# Arduino_S3v3_R2.net
KiCad netlist of a schematic drawn in EAGLE
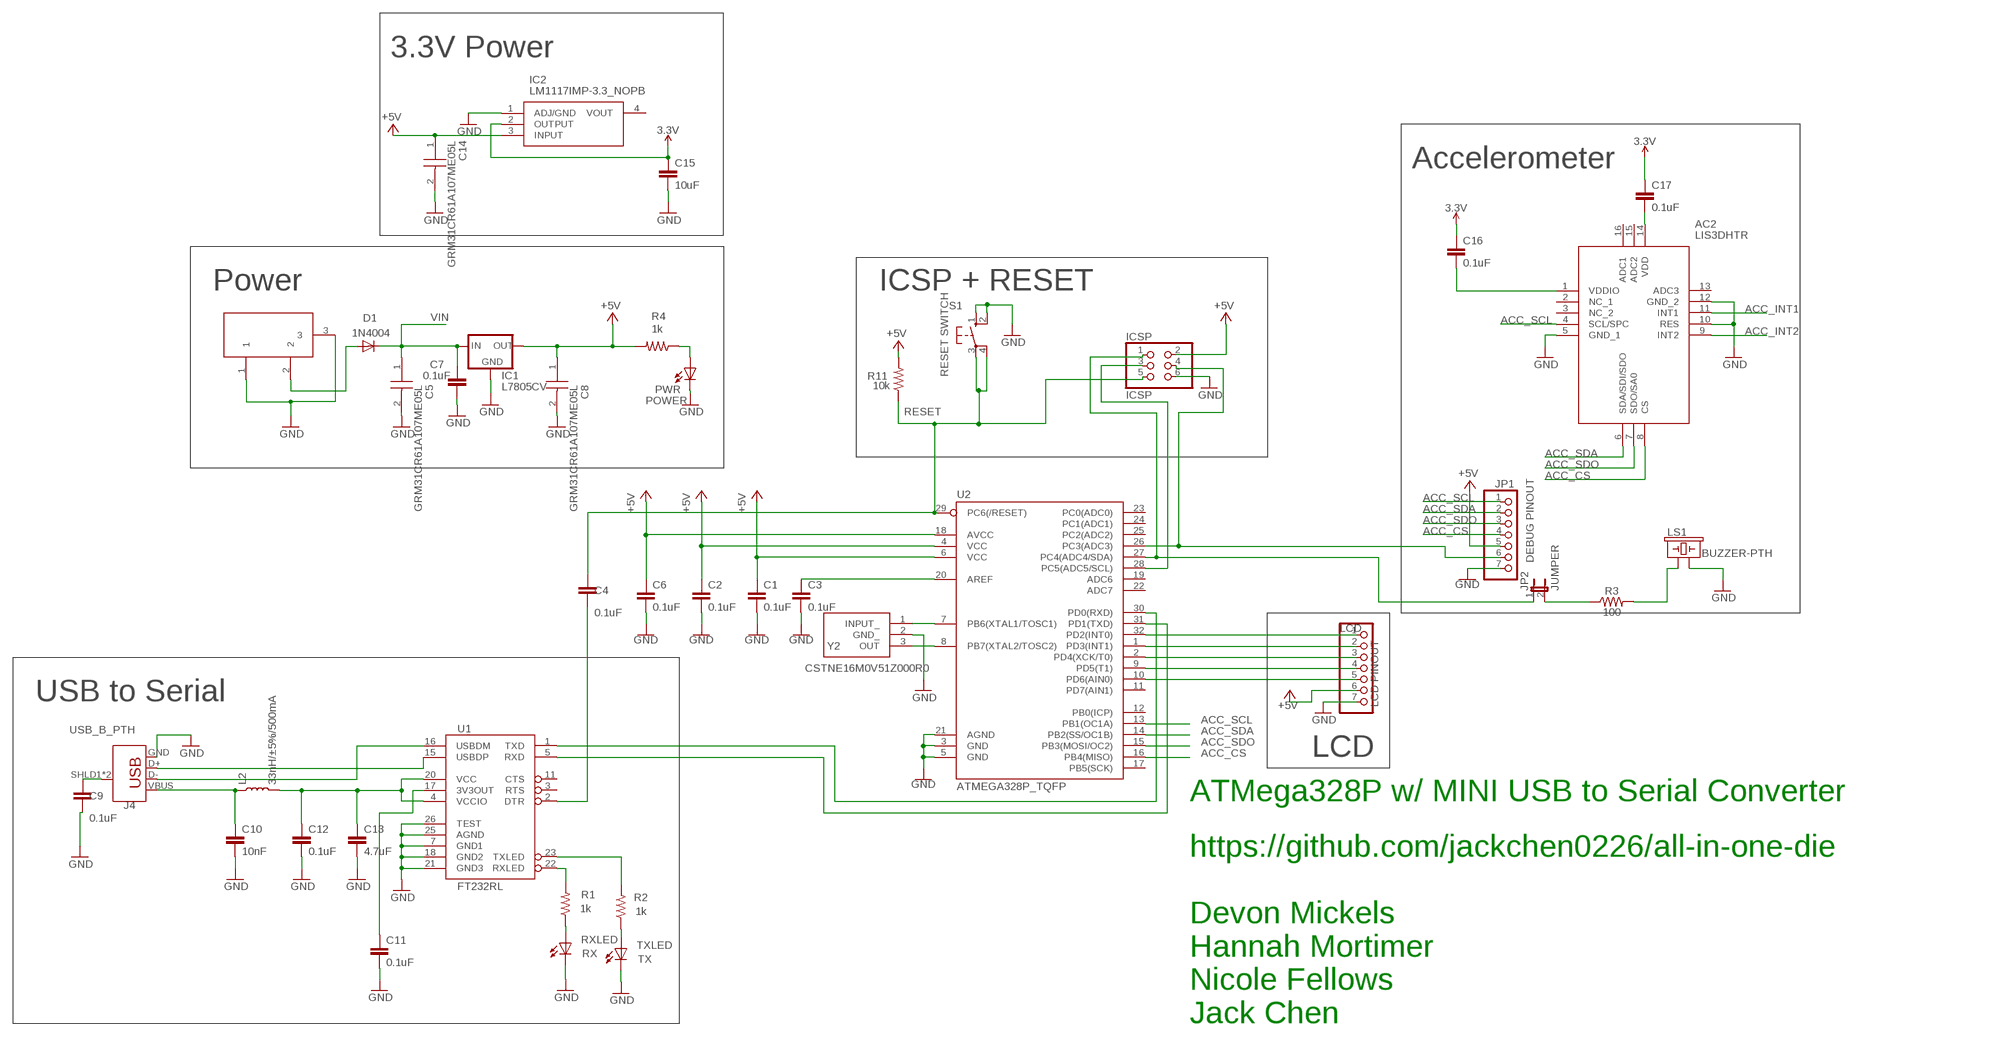
[diagram p0: schematic, sheet 1]

(export (version "E")
  (design (tool "Eeschema 10.0.6"))
  (components
    (comp (ref "AC2")
      (value "LIS3DHTR")
      (footprint "eagle-import:LIS3DHTR")
      (fields (field (name "MOUSER_PART_NUMBER") "511-LIS3DHTR"))
      (libsource (lib "eagle-import") (part "LIS3DHTR"))
    )
    (comp (ref "C1")
      (value "0.1uF")
      (footprint "eagle-import:0603")
      (fields (field (name "MFR") "KEMET") (field (name "MPN") "C0603X104K5RAC3316"))
      (libsource (lib "eagle-import") (part "0.1UF-0603-25V-(+80/-20%)"))
    )
    (comp (ref "C2")
      (value "0.1uF")
      (footprint "eagle-import:0603")
      (fields (field (name "MFR") "KEMET") (field (name "MPN") "C0603X104K5RAC3316"))
      (libsource (lib "eagle-import") (part "0.1UF-0603-25V-(+80/-20%)"))
    )
    (comp (ref "C3")
      (value "0.1uF")
      (footprint "eagle-import:0603")
      (fields (field (name "MFR") "KEMET") (field (name "MPN") "C0603X104K5RAC3316"))
      (libsource (lib "eagle-import") (part "0.1UF-0603-25V-(+80/-20%)"))
    )
    (comp (ref "C4")
      (value "0.1uF")
      (footprint "eagle-import:0603")
      (fields (field (name "MFR") "KEMET") (field (name "MPN") "C0603X104K5RAC3316"))
      (libsource (lib "eagle-import") (part "0.1UF-0603-25V-(+80/-20%)"))
    )
    (comp (ref "C5")
      (value "GRM31CR61A107ME05L")
      (footprint "eagle-import:CAPC3216X180N")
      (fields (field (name "MOUSER_PART_NUMBER") "81-GRM31CR61A107ME5L"))
      (libsource (lib "eagle-import") (part "GRM31CR61A107ME05L"))
    )
    (comp (ref "C6")
      (value "0.1uF")
      (footprint "eagle-import:0603")
      (fields (field (name "MFR") "KEMET") (field (name "MPN") "C0603X104K5RAC3316"))
      (libsource (lib "eagle-import") (part "0.1UF-0603-25V-(+80/-20%)"))
    )
    (comp (ref "C7")
      (value "0.1uF")
      (footprint "eagle-import:0603")
      (fields (field (name "MFR") "KEMET") (field (name "MPN") "C0603X104K5RAC3316"))
      (libsource (lib "eagle-import") (part "0.1UF-0603-25V-(+80/-20%)"))
    )
    (comp (ref "C8")
      (value "GRM31CR61A107ME05L")
      (footprint "eagle-import:CAPC3216X180N")
      (fields (field (name "MOUSER_PART_NUMBER") "81-GRM31CR61A107ME5L"))
      (libsource (lib "eagle-import") (part "GRM31CR61A107ME05L"))
    )
    (comp (ref "C9")
      (value "0.1uF")
      (footprint "eagle-import:0603")
      (fields (field (name "MFR") "KEMET") (field (name "MPN") "C0603X104K5RAC3316"))
      (libsource (lib "eagle-import") (part "0.1UF-0603-25V-(+80/-20%)"))
    )
    (comp (ref "C10")
      (value "10nF")
      (footprint "eagle-import:0603")
      (fields (field (name "MFR") "KEMET") (field (name "MPN") "C0603C103K5RAC7013"))
      (libsource (lib "eagle-import") (part "10NF-0603-50V-10%"))
    )
    (comp (ref "C11")
      (value "0.1uF")
      (footprint "eagle-import:0603")
      (fields (field (name "MFR") "KEMET") (field (name "MPN") "C0603X104K5RAC3316"))
      (libsource (lib "eagle-import") (part "0.1UF-0603-25V-(+80/-20%)"))
    )
    (comp (ref "C12")
      (value "0.1uF")
      (footprint "eagle-import:0603")
      (fields (field (name "MFR") "KEMET") (field (name "MPN") "C0603X104K5RAC3316"))
      (libsource (lib "eagle-import") (part "0.1UF-0603-25V-(+80/-20%)"))
    )
    (comp (ref "C13")
      (value "4.7uF")
      (footprint "eagle-import:0603")
      (fields (field (name "MFR") "Taiyo Yuden") (field (name "MPN") "LMK107BJ475MAHT"))
      (libsource (lib "eagle-import") (part "4.7UF0603"))
    )
    (comp (ref "C14")
      (value "GRM31CR61A107ME05L")
      (footprint "eagle-import:CAPC3216X180N")
      (fields (field (name "MOUSER_PART_NUMBER") "81-GRM31CR61A107ME5L"))
      (libsource (lib "eagle-import") (part "GRM31CR61A107ME05L"))
    )
    (comp (ref "C15")
      (value "10uF")
      (footprint "eagle-import:0603")
      (fields (field (name "MFR") "Murata Electronics") (field (name "MPN") "GRM188R61E106KA73D"))
      (libsource (lib "eagle-import") (part "10UF-0603-6.3V-20%"))
    )
    (comp (ref "C16")
      (value "0.1uF")
      (footprint "eagle-import:0603")
      (fields (field (name "MFR") "KEMET") (field (name "MPN") "C0603X104K5RAC3316"))
      (libsource (lib "eagle-import") (part "0.1UF-0603-25V-(+80/-20%)"))
    )
    (comp (ref "C17")
      (value "0.1uF")
      (footprint "eagle-import:0603")
      (fields (field (name "MFR") "KEMET") (field (name "MPN") "C0603X104K5RAC3316"))
      (libsource (lib "eagle-import") (part "0.1UF-0603-25V-(+80/-20%)"))
    )
    (comp (ref "D1")
      (value "1N4004")
      (footprint "eagle-import:DO41-10")
      (fields (field (name "MFR") "Diodes Incorporated") (field (name "MPN") "1N4004-T"))
      (libsource (lib "eagle-import") (part "1N4004"))
    )
    (comp (ref "DC1")
      (value "DC21MMX")
      (footprint "eagle-import:DC-21MM")
      (fields (field (name "MFR") "Gravitech") (field (name "MPN") "CON-SOCJ-2155"))
      (libsource (lib "eagle-import") (part "DC21MMX"))
    )
    (comp (ref "IC1")
      (value "L7805CV")
      (footprint "eagle-import:78XXS")
      (fields (field (name "MFR") "STMicroelectronics"))
      (libsource (lib "eagle-import") (part "78XXS"))
    )
    (comp (ref "IC2")
      (value "LM1117IMP-3.3_NOPB")
      (footprint "eagle-import:SOT230P700X180-4N")
      (fields
        (field (name "MANUFACTURER_PART_NUMBER") "LM1117IMP-3.3/NOPB")
        (field (name "MOUSER_PART_NUMBER") "926-LM1117IMP3.3NOPB")
      )
      (libsource (lib "eagle-import") (part "LM1117IMP-3.3_NOPB"))
    )
    (comp (ref "ICSP")
      (value "ICSP")
      (footprint "eagle-import:2X03")
      (fields (field (name "MFR") "Harwin") (field (name "MPN") "M20-9980346"))
      (libsource (lib "eagle-import") (part "PINHD-2X3"))
    )
    (comp (ref "J4")
      (value "USB_B_PTH")
      (footprint "eagle-import:USB-B-PTH")
      (fields (field (name "MFR") "Amphenol FCI") (field (name "MPN") "61729-0010BLF"))
      (libsource (lib "eagle-import") (part "USB_B_PTH"))
    )
    (comp (ref "JP1")
      (value "DEBUG PINOUT")
      (footprint "eagle-import:1X07")
      (fields (field (name "MFR") "Harwin") (field (name "MPN") "M20-9770746"))
      (libsource (lib "eagle-import") (part "PINHD-1X7"))
    )
    (comp (ref "JP2")
      (value "JUMPER")
      (footprint "eagle-import:JP1")
      (fields (field (name "MFR") "Harwin") (field (name "MPN") "M20-9990246"))
      (libsource (lib "eagle-import") (part "JP1E"))
    )
    (comp (ref "L2")
      (value "33nH/±5%/500mA")
      (footprint "eagle-import:0603")
      (fields (field (name "MFR") "Murata Electronics") (field (name "MPN") "LQW18AS33NJ0CD"))
      (libsource (lib "eagle-import") (part "INDUCTOR-0603-33NH"))
    )
    (comp (ref "LCD")
      (value "LCD PINOUT")
      (footprint "eagle-import:1X07")
      (fields (field (name "MFR") "Harwin") (field (name "MPN") "M20-9770746"))
      (libsource (lib "eagle-import") (part "PINHD-1X7"))
    )
    (comp (ref "LS1")
      (value "BUZZER-PTH")
      (footprint "eagle-import:BUZZER-12MM")
      (fields (field (name "MFR") "TDK") (field (name "MPN") "SD1209T5-A1"))
      (libsource (lib "eagle-import") (part "BUZZER-PTH"))
    )
    (comp (ref "PWR")
      (value "POWER")
      (footprint "eagle-import:LED3MM")
      (fields (field (name "MFR") "VCC") (field (name "MPN") "LTH3MM12VFR4100"))
      (libsource (lib "eagle-import") (part "LED3MM"))
    )
    (comp (ref "R1")
      (value "1k")
      (footprint "eagle-import:0603")
      (fields (field (name "MFR") "Vishay / Dale") (field (name "MPN") "RCC06031K00FKEA"))
      (libsource (lib "eagle-import") (part "1KOHM-0603-1/10W-1%"))
    )
    (comp (ref "R2")
      (value "1k")
      (footprint "eagle-import:0603")
      (fields (field (name "MFR") "Vishay / Dale") (field (name "MPN") "RCC06031K00FKEA"))
      (libsource (lib "eagle-import") (part "1KOHM-0603-1/10W-1%"))
    )
    (comp (ref "R3")
      (value "100")
      (footprint "eagle-import:0603")
      (fields (field (name "MFR") "Vishay / Dale") (field (name "MPN") "RCC0603100RFKEA"))
      (libsource (lib "eagle-import") (part "100OHM-0603-1/4W-5%"))
    )
    (comp (ref "R4")
      (value "1k")
      (footprint "eagle-import:0603")
      (fields (field (name "MFR") "Vishay / Dale") (field (name "MPN") "RCC06031K00FKEA"))
      (libsource (lib "eagle-import") (part "1KOHM-0603-1/10W-1%"))
    )
    (comp (ref "R11")
      (value "10k")
      (footprint "eagle-import:0603")
      (fields (field (name "MFR") "Panasonic") (field (name "MPN") "ERJ-UP3D1002V"))
      (libsource (lib "eagle-import") (part "10KOHM-0603-1/10W-1%"))
    )
    (comp (ref "RXLED")
      (value "RX")
      (footprint "eagle-import:LED3MM")
      (fields (field (name "MFR") "VCC") (field (name "MPN") "LTH3MM12VFR4500"))
      (libsource (lib "eagle-import") (part "LED3MM"))
    )
    (comp (ref "S1")
      (value "RESET SWITCH")
      (footprint "eagle-import:B3F-10XX")
      (fields (field (name "MFR") "Omron Electronics") (field (name "MPN") "B3F-1000"))
      (libsource (lib "eagle-import") (part "10-XX"))
    )
    (comp (ref "TXLED")
      (value "TX")
      (footprint "eagle-import:LED3MM")
      (fields (field (name "MFR") "VCC") (field (name "MPN") "LTH3MM12VFR4500"))
      (libsource (lib "eagle-import") (part "LED3MM"))
    )
    (comp (ref "U1")
      (value "FT232RL")
      (footprint "eagle-import:SSOP28DB")
      (fields (field (name "MFR") "FTDI") (field (name "MPN") "FT232RL-REEL"))
      (libsource (lib "eagle-import") (part "FT232RL-BASICSSOP"))
    )
    (comp (ref "U2")
      (value "ATMEGA328P_TQFP")
      (footprint "eagle-import:TQFP32-08")
      (fields (field (name "MFR") "Microchip Technology / Atmel") (field (name "MPN") "ATMEGA328P-AU"))
      (libsource (lib "eagle-import") (part "ATMEGA328P_TQFP"))
    )
    (comp (ref "Y2")
      (value "CSTNE16M0V51Z000R0")
      (footprint "eagle-import:CSTNE16M0V51Z000R0")
      (fields (field (name "MOUSER_PART_NUMBER") "81-CSTNE16M0V51Z000R"))
      (libsource (lib "eagle-import") (part "CSTNE16M0V51Z000R0"))
    )
  )
  (nets
    (net (code "1") (name "+5V") (class "Default")
      (node (ref "C1") (pin "1") (pinfunction "1_1") (pintype "passive"))
      (node (ref "C14") (pin "1") (pinfunction "1_1") (pintype "bidirectional"))
      (node (ref "C2") (pin "1") (pinfunction "1_1") (pintype "passive"))
      (node (ref "C6") (pin "1") (pinfunction "1_1") (pintype "passive"))
      (node (ref "C8") (pin "1") (pinfunction "1_1") (pintype "bidirectional"))
      (node (ref "IC1") (pin "OUT") (pinfunction "OUT_OUT") (pintype "passive"))
      (node (ref "IC2") (pin "3") (pinfunction "INPUT_3") (pintype "bidirectional"))
      (node (ref "ICSP") (pin "2") (pinfunction "2_2") (pintype "passive"))
      (node (ref "JP1") (pin "5") (pinfunction "5_5") (pintype "passive"))
      (node (ref "LCD") (pin "6") (pinfunction "6_6") (pintype "passive"))
      (node (ref "R11") (pin "2") (pinfunction "2_2") (pintype "passive"))
      (node (ref "R4") (pin "2") (pinfunction "2_2") (pintype "passive"))
      (node (ref "U2") (pin "18") (pinfunction "AVCC_18") (pintype "bidirectional"))
      (node (ref "U2") (pin "4") (pinfunction "VCC_4") (pintype "bidirectional"))
      (node (ref "U2") (pin "6") (pinfunction "VCC_6") (pintype "bidirectional"))
    )
    (net (code "2") (name "/ACC_CS") (class "Default")
      (node (ref "AC2") (pin "8") (pinfunction "CS_8") (pintype "input"))
      (node (ref "JP1") (pin "4") (pinfunction "4_4") (pintype "passive"))
      (node (ref "U2") (pin "16") (pinfunction "PB4(MISO)_16") (pintype "bidirectional"))
    )
    (net (code "3") (name "/ACC_INT1") (class "Default")
      (node (ref "AC2") (pin "11") (pinfunction "INT1_11") (pintype "input"))
    )
    (net (code "4") (name "/ACC_INT2") (class "Default")
      (node (ref "AC2") (pin "9") (pinfunction "INT2_9") (pintype "input"))
    )
    (net (code "5") (name "/ACC_SCL") (class "Default")
      (node (ref "AC2") (pin "4") (pinfunction "SCL/SPC_4") (pintype "bidirectional"))
      (node (ref "JP1") (pin "1") (pinfunction "1_1") (pintype "passive"))
      (node (ref "U2") (pin "13") (pinfunction "PB1(OC1A)_13") (pintype "bidirectional"))
    )
    (net (code "6") (name "/ACC_SDA") (class "Default")
      (node (ref "AC2") (pin "6") (pinfunction "SDA/SDI/SDO_6") (pintype "bidirectional"))
      (node (ref "JP1") (pin "2") (pinfunction "2_2") (pintype "passive"))
      (node (ref "U2") (pin "14") (pinfunction "PB2(SS/OC1B)_14") (pintype "bidirectional"))
    )
    (net (code "7") (name "/ACC_SDO") (class "Default")
      (node (ref "AC2") (pin "7") (pinfunction "SDO/SA0_7") (pintype "bidirectional"))
      (node (ref "JP1") (pin "3") (pinfunction "3_3") (pintype "passive"))
      (node (ref "U2") (pin "15") (pinfunction "PB3(MOSI/OC2)_15") (pintype "bidirectional"))
    )
    (net (code "8") (name "/RESET") (class "Default")
      (node (ref "C4") (pin "1") (pinfunction "1_1") (pintype "passive"))
      (node (ref "ICSP") (pin "5") (pinfunction "5_5") (pintype "passive"))
      (node (ref "R11") (pin "1") (pinfunction "1_1") (pintype "passive"))
      (node (ref "S1") (pin "3") (pinfunction "P_3") (pintype "passive"))
      (node (ref "S1") (pin "4") (pinfunction "P1_4") (pintype "passive"))
      (node (ref "U2") (pin "29") (pinfunction "PC6(/RESET)_29") (pintype "bidirectional"))
    )
    (net (code "9") (name "/VIN") (class "Default")
      (node (ref "C5") (pin "1") (pinfunction "1_1") (pintype "bidirectional"))
      (node (ref "C7") (pin "2") (pinfunction "2_2") (pintype "passive"))
      (node (ref "D1") (pin "C") (pinfunction "C_C") (pintype "passive"))
      (node (ref "IC1") (pin "IN") (pinfunction "IN_IN") (pintype "input"))
    )
    (net (code "10") (name "3.3V") (class "Default")
      (node (ref "C15") (pin "1") (pinfunction "1_1") (pintype "passive"))
      (node (ref "C16") (pin "1") (pinfunction "1_1") (pintype "passive"))
      (node (ref "C17") (pin "1") (pinfunction "1_1") (pintype "passive"))
      (node (ref "IC2") (pin "2") (pinfunction "OUTPUT_2") (pintype "bidirectional"))
    )
    (net (code "11") (name "GND") (class "Default")
      (node (ref "AC2") (pin "10") (pinfunction "RES_10") (pintype "bidirectional"))
      (node (ref "AC2") (pin "12") (pinfunction "GND_2_12") (pintype "power_in"))
      (node (ref "AC2") (pin "5") (pinfunction "GND_1_5") (pintype "power_in"))
      (node (ref "C1") (pin "2") (pinfunction "2_2") (pintype "passive"))
      (node (ref "C10") (pin "2") (pinfunction "2_2") (pintype "passive"))
      (node (ref "C11") (pin "2") (pinfunction "2_2") (pintype "passive"))
      (node (ref "C12") (pin "2") (pinfunction "2_2") (pintype "passive"))
      (node (ref "C13") (pin "2") (pinfunction "2_2") (pintype "passive"))
      (node (ref "C14") (pin "2") (pinfunction "2_2") (pintype "bidirectional"))
      (node (ref "C15") (pin "2") (pinfunction "2_2") (pintype "passive"))
      (node (ref "C2") (pin "2") (pinfunction "2_2") (pintype "passive"))
      (node (ref "C3") (pin "2") (pinfunction "2_2") (pintype "passive"))
      (node (ref "C5") (pin "2") (pinfunction "2_2") (pintype "bidirectional"))
      (node (ref "C6") (pin "2") (pinfunction "2_2") (pintype "passive"))
      (node (ref "C7") (pin "1") (pinfunction "1_1") (pintype "passive"))
      (node (ref "C8") (pin "2") (pinfunction "2_2") (pintype "bidirectional"))
      (node (ref "C9") (pin "2") (pinfunction "2_2") (pintype "passive"))
      (node (ref "DC1") (pin "1") (pinfunction "1_1") (pintype "power_in"))
      (node (ref "DC1") (pin "3") (pinfunction "3_3") (pintype "power_in"))
      (node (ref "IC1") (pin "GND") (pinfunction "GND_GND") (pintype "input"))
      (node (ref "IC2") (pin "1") (pinfunction "ADJ/GND_1") (pintype "bidirectional"))
      (node (ref "ICSP") (pin "6") (pinfunction "6_6") (pintype "passive"))
      (node (ref "J4") (pin "GND") (pinfunction "GND_GND") (pintype "power_in"))
      (node (ref "JP1") (pin "7") (pinfunction "7_7") (pintype "passive"))
      (node (ref "LCD") (pin "7") (pinfunction "7_7") (pintype "passive"))
      (node (ref "LS1") (pin "-") (pinfunction "2_-") (pintype "passive"))
      (node (ref "PWR") (pin "K") (pinfunction "C_K") (pintype "passive"))
      (node (ref "RXLED") (pin "K") (pinfunction "C_K") (pintype "passive"))
      (node (ref "S1") (pin "1") (pinfunction "S_1") (pintype "passive"))
      (node (ref "S1") (pin "2") (pinfunction "S1_2") (pintype "passive"))
      (node (ref "TXLED") (pin "K") (pinfunction "C_K") (pintype "passive"))
      (node (ref "U1") (pin "18") (pinfunction "GND2_18") (pintype "power_in"))
      (node (ref "U1") (pin "21") (pinfunction "GND3_21") (pintype "power_in"))
      (node (ref "U1") (pin "25") (pinfunction "AGND_25") (pintype "power_in"))
      (node (ref "U1") (pin "26") (pinfunction "TEST_26") (pintype "input"))
      (node (ref "U1") (pin "7") (pinfunction "GND1_7") (pintype "power_in"))
      (node (ref "U2") (pin "21") (pinfunction "AGND_21") (pintype "bidirectional"))
      (node (ref "U2") (pin "3") (pinfunction "GND_3") (pintype "bidirectional"))
      (node (ref "U2") (pin "5") (pinfunction "GND_5") (pintype "bidirectional"))
      (node (ref "Y2") (pin "2") (pinfunction "GND__2") (pintype "bidirectional"))
    )
    (net (code "12") (name "Net-(AC2-VDD)") (class "Default")
      (node (ref "AC2") (pin "14") (pinfunction "VDD_14") (pintype "power_in"))
      (node (ref "C17") (pin "2") (pinfunction "2_2") (pintype "passive"))
    )
    (net (code "13") (name "Net-(AC2-VDDIO)") (class "Default")
      (node (ref "AC2") (pin "1") (pinfunction "VDDIO_1") (pintype "power_in"))
      (node (ref "C16") (pin "2") (pinfunction "2_2") (pintype "passive"))
    )
    (net (code "14") (name "Net-(C9-Pad1)") (class "Default")
      (node (ref "C9") (pin "1") (pinfunction "1_1") (pintype "passive"))
      (node (ref "J4") (pin "SHLD1") (pinfunction "SHIELD_SHLD1") (pintype "bidirectional"))
      (node (ref "J4") (pin "SHLD2") (pinfunction "SHIELD_SHLD2") (pintype "bidirectional"))
    )
    (net (code "15") (name "Net-(C10-Pad1)") (class "Default")
      (node (ref "C10") (pin "1") (pinfunction "1_1") (pintype "passive"))
      (node (ref "J4") (pin "VBUS") (pinfunction "VBUS_VBUS") (pintype "power_in"))
      (node (ref "L2") (pin "1") (pinfunction "1_1") (pintype "passive"))
    )
    (net (code "16") (name "Net-(D1-PadA)") (class "Default")
      (node (ref "D1") (pin "A") (pinfunction "A_A") (pintype "passive"))
      (node (ref "DC1") (pin "2") (pinfunction "2_2") (pintype "power_in"))
    )
    (net (code "17") (name "Net-(JP2-Pad2)") (class "Default")
      (node (ref "JP2") (pin "2") (pinfunction "2_2") (pintype "passive"))
      (node (ref "R3") (pin "1") (pinfunction "1_1") (pintype "passive"))
    )
    (net (code "18") (name "Net-(LS1-1)") (class "Default")
      (node (ref "LS1") (pin "+") (pinfunction "1_+") (pintype "passive"))
      (node (ref "R3") (pin "2") (pinfunction "2_2") (pintype "passive"))
    )
    (net (code "19") (name "Net-(PWR-PadA)") (class "Default")
      (node (ref "PWR") (pin "A") (pinfunction "A_A") (pintype "passive"))
      (node (ref "R4") (pin "1") (pinfunction "1_1") (pintype "passive"))
    )
    (net (code "20") (name "Net-(R1-Pad1)") (class "Default")
      (node (ref "R1") (pin "1") (pinfunction "1_1") (pintype "passive"))
      (node (ref "RXLED") (pin "A") (pinfunction "A_A") (pintype "passive"))
    )
    (net (code "21") (name "Net-(R2-Pad1)") (class "Default")
      (node (ref "R2") (pin "1") (pinfunction "1_1") (pintype "passive"))
      (node (ref "TXLED") (pin "A") (pinfunction "A_A") (pintype "passive"))
    )
    (net (code "22") (name "Net-(U1-3V3OUT)") (class "Default")
      (node (ref "C11") (pin "1") (pinfunction "1_1") (pintype "passive"))
      (node (ref "U1") (pin "17") (pinfunction "3V3OUT_17") (pintype "output"))
    )
    (net (code "23") (name "Net-(U1-DTR)") (class "Default")
      (node (ref "C4") (pin "2") (pinfunction "2_2") (pintype "passive"))
      (node (ref "U1") (pin "2") (pinfunction "DTR_2") (pintype "bidirectional"))
    )
    (net (code "24") (name "Net-(U1-RXD)") (class "Default")
      (node (ref "U1") (pin "5") (pinfunction "RXD_5") (pintype "input"))
      (node (ref "U2") (pin "31") (pinfunction "PD1(TXD)_31") (pintype "bidirectional"))
    )
    (net (code "25") (name "Net-(U1-RXLED)") (class "Default")
      (node (ref "R1") (pin "2") (pinfunction "2_2") (pintype "passive"))
      (node (ref "U1") (pin "22") (pinfunction "RXLED_22") (pintype "bidirectional"))
    )
    (net (code "26") (name "Net-(U1-TXD)") (class "Default")
      (node (ref "U1") (pin "1") (pinfunction "TXD_1") (pintype "output"))
      (node (ref "U2") (pin "30") (pinfunction "PD0(RXD)_30") (pintype "bidirectional"))
    )
    (net (code "27") (name "Net-(U1-TXLED)") (class "Default")
      (node (ref "R2") (pin "2") (pinfunction "2_2") (pintype "passive"))
      (node (ref "U1") (pin "23") (pinfunction "TXLED_23") (pintype "bidirectional"))
    )
    (net (code "28") (name "Net-(U1-USBDM)") (class "Default")
      (node (ref "J4") (pin "D-") (pinfunction "D-_D-") (pintype "bidirectional"))
      (node (ref "U1") (pin "16") (pinfunction "USBDM_16") (pintype "bidirectional"))
    )
    (net (code "29") (name "Net-(U1-USBDP)") (class "Default")
      (node (ref "J4") (pin "D+") (pinfunction "D+_D+") (pintype "bidirectional"))
      (node (ref "U1") (pin "15") (pinfunction "USBDP_15") (pintype "bidirectional"))
    )
    (net (code "30") (name "Net-(U1-VCC)") (class "Default")
      (node (ref "C12") (pin "1") (pinfunction "1_1") (pintype "passive"))
      (node (ref "C13") (pin "1") (pinfunction "1_1") (pintype "passive"))
      (node (ref "L2") (pin "2") (pinfunction "2_2") (pintype "passive"))
      (node (ref "U1") (pin "20") (pinfunction "VCC_20") (pintype "power_in"))
      (node (ref "U1") (pin "4") (pinfunction "VCCIO_4") (pintype "power_in"))
    )
    (net (code "31") (name "Net-(U2-AREF)") (class "Default")
      (node (ref "C3") (pin "1") (pinfunction "1_1") (pintype "passive"))
      (node (ref "U2") (pin "20") (pinfunction "AREF_20") (pintype "bidirectional"))
    )
    (net (code "32") (name "Net-(U2-PB6(XTAL1{slash}TOSC1))") (class "Default")
      (node (ref "U2") (pin "7") (pinfunction "PB6(XTAL1/TOSC1)_7") (pintype "bidirectional"))
      (node (ref "Y2") (pin "1") (pinfunction "INPUT__1") (pintype "bidirectional"))
    )
    (net (code "33") (name "Net-(U2-PB7(XTAL2{slash}TOSC2))") (class "Default")
      (node (ref "U2") (pin "8") (pinfunction "PB7(XTAL2/TOSC2)_8") (pintype "bidirectional"))
      (node (ref "Y2") (pin "3") (pinfunction "OUT_3") (pintype "bidirectional"))
    )
    (net (code "34") (name "Net-(U2-PC3(ADC3))") (class "Default")
      (node (ref "ICSP") (pin "4") (pinfunction "4_4") (pintype "passive"))
      (node (ref "JP1") (pin "6") (pinfunction "6_6") (pintype "passive"))
      (node (ref "U2") (pin "26") (pinfunction "PC3(ADC3)_26") (pintype "bidirectional"))
    )
    (net (code "35") (name "Net-(U2-PC4(ADC4{slash}SDA))") (class "Default")
      (node (ref "ICSP") (pin "1") (pinfunction "1_1") (pintype "passive"))
      (node (ref "JP2") (pin "1") (pinfunction "1_1") (pintype "passive"))
      (node (ref "U2") (pin "27") (pinfunction "PC4(ADC4/SDA)_27") (pintype "bidirectional"))
    )
    (net (code "36") (name "Net-(U2-PC5(ADC5{slash}SCL))") (class "Default")
      (node (ref "ICSP") (pin "3") (pinfunction "3_3") (pintype "passive"))
      (node (ref "U2") (pin "28") (pinfunction "PC5(ADC5/SCL)_28") (pintype "bidirectional"))
    )
    (net (code "37") (name "Net-(U2-PD2(INT0))") (class "Default")
      (node (ref "LCD") (pin "1") (pinfunction "1_1") (pintype "passive"))
      (node (ref "U2") (pin "32") (pinfunction "PD2(INT0)_32") (pintype "bidirectional"))
    )
    (net (code "38") (name "Net-(U2-PD3(INT1))") (class "Default")
      (node (ref "LCD") (pin "2") (pinfunction "2_2") (pintype "passive"))
      (node (ref "U2") (pin "1") (pinfunction "PD3(INT1)_1") (pintype "bidirectional"))
    )
    (net (code "39") (name "Net-(U2-PD4(XCK{slash}T0))") (class "Default")
      (node (ref "LCD") (pin "3") (pinfunction "3_3") (pintype "passive"))
      (node (ref "U2") (pin "2") (pinfunction "PD4(XCK/T0)_2") (pintype "bidirectional"))
    )
    (net (code "40") (name "Net-(U2-PD5(T1))") (class "Default")
      (node (ref "LCD") (pin "4") (pinfunction "4_4") (pintype "passive"))
      (node (ref "U2") (pin "9") (pinfunction "PD5(T1)_9") (pintype "bidirectional"))
    )
    (net (code "41") (name "Net-(U2-PD6(AIN0))") (class "Default")
      (node (ref "LCD") (pin "5") (pinfunction "5_5") (pintype "passive"))
      (node (ref "U2") (pin "10") (pinfunction "PD6(AIN0)_10") (pintype "bidirectional"))
    )
    (net (code "42") (name "unconnected-(AC2-ADC1-Pad16)") (class "Default")
      (node (ref "AC2") (pin "16") (pinfunction "ADC1_16") (pintype "bidirectional"))
    )
    (net (code "43") (name "unconnected-(AC2-ADC2-Pad15)") (class "Default")
      (node (ref "AC2") (pin "15") (pinfunction "ADC2_15") (pintype "bidirectional"))
    )
    (net (code "44") (name "unconnected-(AC2-ADC3-Pad13)") (class "Default")
      (node (ref "AC2") (pin "13") (pinfunction "ADC3_13") (pintype "bidirectional"))
    )
    (net (code "45") (name "unconnected-(AC2-NC_1-Pad2)") (class "Default")
      (node (ref "AC2") (pin "2") (pinfunction "NC_1_2") (pintype "bidirectional"))
    )
    (net (code "46") (name "unconnected-(AC2-NC_2-Pad3)") (class "Default")
      (node (ref "AC2") (pin "3") (pinfunction "NC_2_3") (pintype "bidirectional"))
    )
    (net (code "47") (name "unconnected-(IC2-VOUT-Pad4)") (class "Default")
      (node (ref "IC2") (pin "4") (pinfunction "VOUT_4") (pintype "bidirectional"))
    )
    (net (code "48") (name "unconnected-(U1-CTS-Pad11)") (class "Default")
      (node (ref "U1") (pin "11") (pinfunction "CTS_11") (pintype "bidirectional"))
    )
    (net (code "49") (name "unconnected-(U1-RTS-Pad3)") (class "Default")
      (node (ref "U1") (pin "3") (pinfunction "RTS_3") (pintype "bidirectional"))
    )
    (net (code "50") (name "unconnected-(U2-ADC6-Pad19)") (class "Default")
      (node (ref "U2") (pin "19") (pinfunction "ADC6_19") (pintype "bidirectional"))
    )
    (net (code "51") (name "unconnected-(U2-ADC7-Pad22)") (class "Default")
      (node (ref "U2") (pin "22") (pinfunction "ADC7_22") (pintype "bidirectional"))
    )
    (net (code "52") (name "unconnected-(U2-PB0(ICP)-Pad12)") (class "Default")
      (node (ref "U2") (pin "12") (pinfunction "PB0(ICP)_12") (pintype "bidirectional"))
    )
    (net (code "53") (name "unconnected-(U2-PB5(SCK)-Pad17)") (class "Default")
      (node (ref "U2") (pin "17") (pinfunction "PB5(SCK)_17") (pintype "bidirectional"))
    )
    (net (code "54") (name "unconnected-(U2-PC0(ADC0)-Pad23)") (class "Default")
      (node (ref "U2") (pin "23") (pinfunction "PC0(ADC0)_23") (pintype "bidirectional"))
    )
    (net (code "55") (name "unconnected-(U2-PC1(ADC1)-Pad24)") (class "Default")
      (node (ref "U2") (pin "24") (pinfunction "PC1(ADC1)_24") (pintype "bidirectional"))
    )
    (net (code "56") (name "unconnected-(U2-PC2(ADC2)-Pad25)") (class "Default")
      (node (ref "U2") (pin "25") (pinfunction "PC2(ADC2)_25") (pintype "bidirectional"))
    )
    (net (code "57") (name "unconnected-(U2-PD7(AIN1)-Pad11)") (class "Default")
      (node (ref "U2") (pin "11") (pinfunction "PD7(AIN1)_11") (pintype "bidirectional"))
    )
  )
)
